# control_board.net
KiCad netlist of a schematic drawn in EAGLE
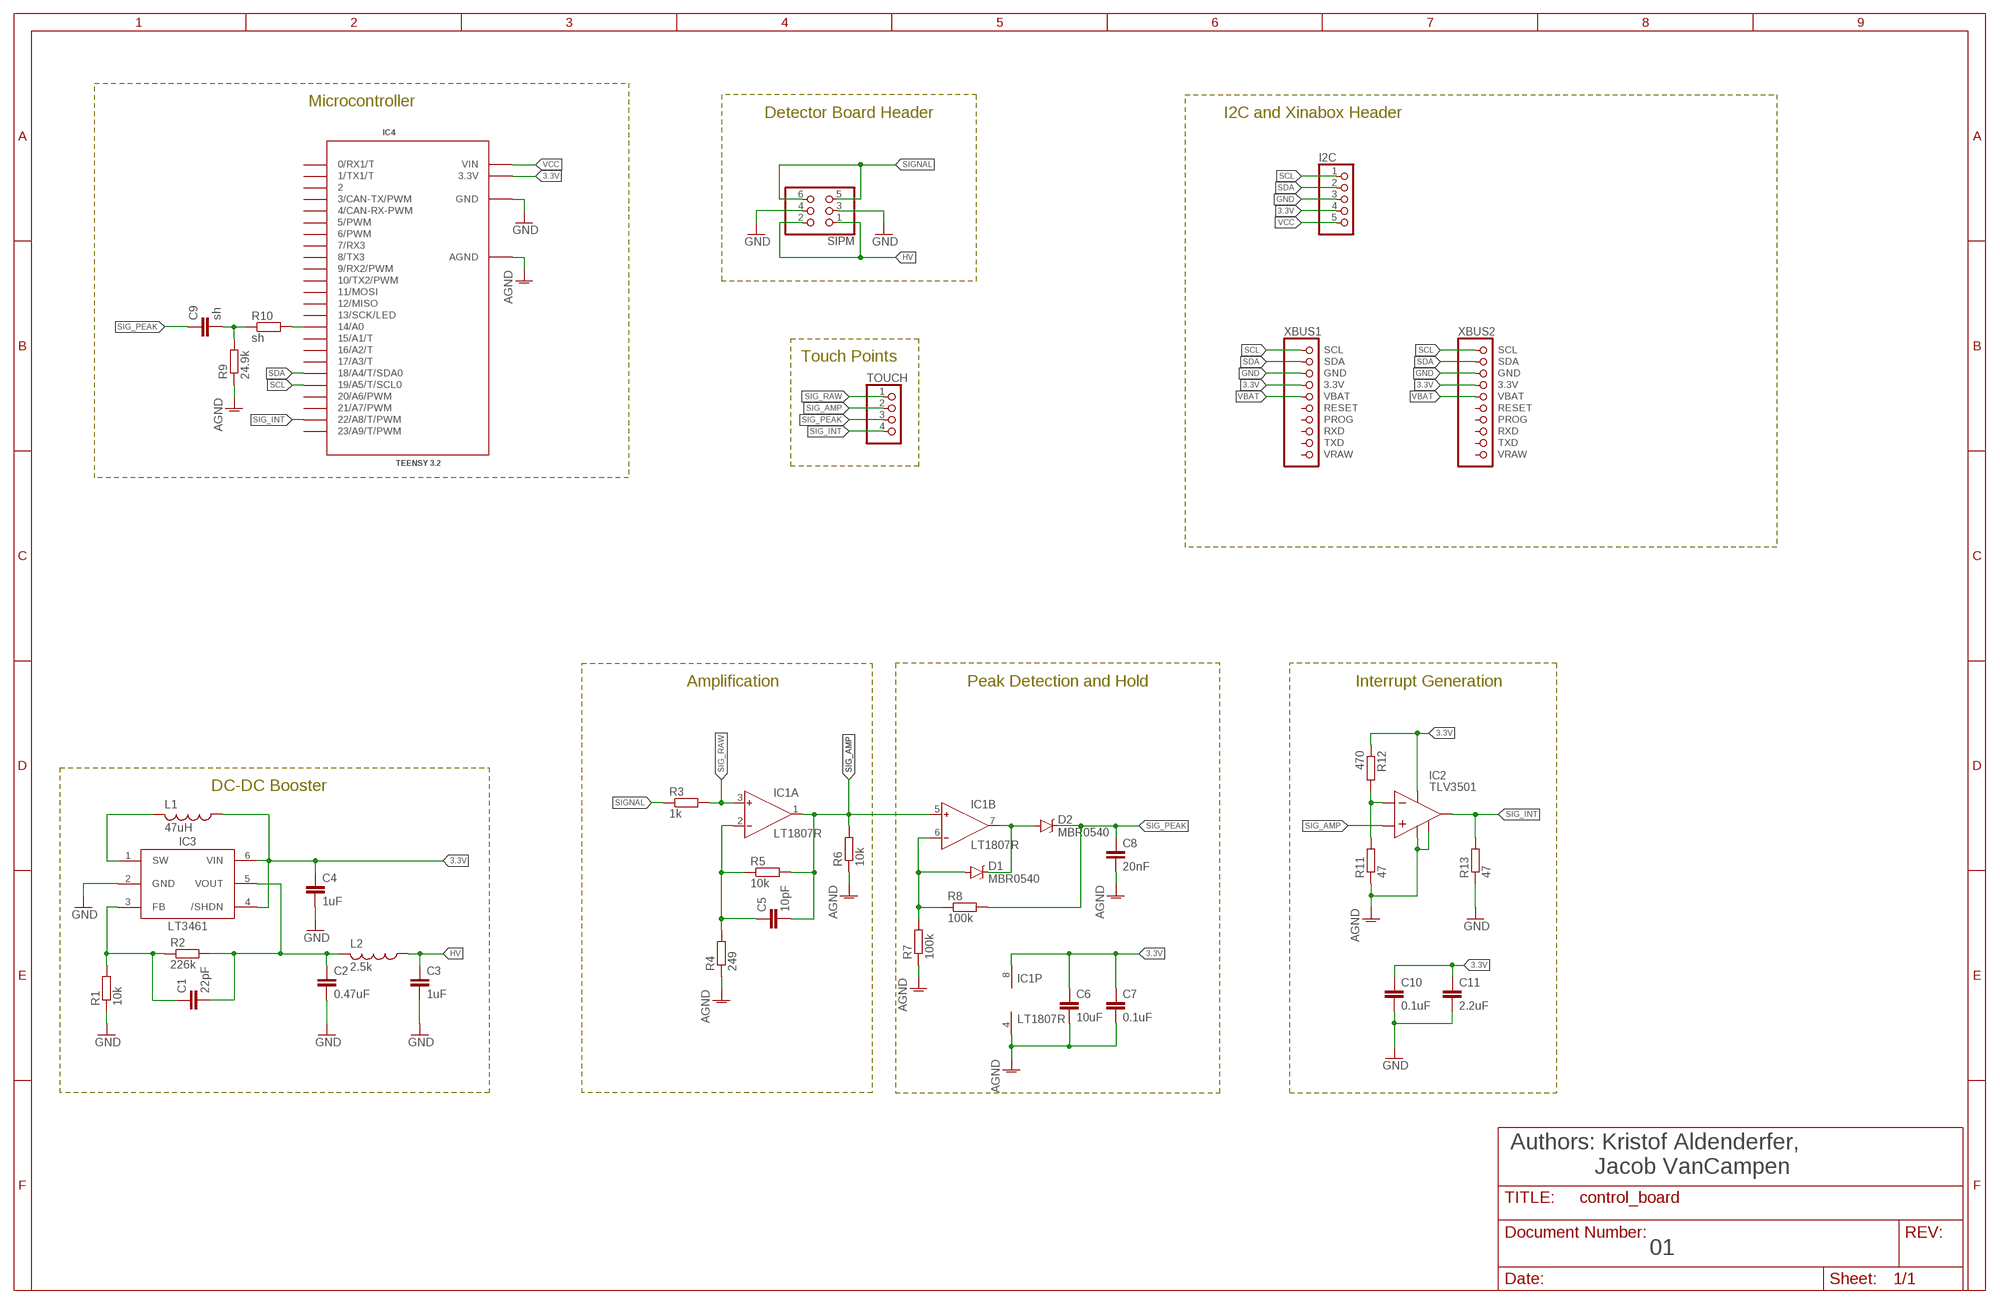
[diagram p0: schematic, sheet 1]

(export (version "E")
  (design (tool "Eeschema 10.0.6"))
  (components
    (comp (ref "C1")
      (value "22pF")
      (footprint "eagle-import:C0805K")
      (libsource (lib "eagle-import") (part "C-EUC0805K"))
    )
    (comp (ref "C2")
      (value "0.47uF")
      (footprint "eagle-import:C0805K")
      (libsource (lib "eagle-import") (part "C-EUC0805K"))
    )
    (comp (ref "C3")
      (value "1uF")
      (footprint "eagle-import:C0805K")
      (libsource (lib "eagle-import") (part "C-EUC0805K"))
    )
    (comp (ref "C4")
      (value "1uF")
      (footprint "eagle-import:C0805K")
      (libsource (lib "eagle-import") (part "C-EUC0805K"))
    )
    (comp (ref "C5")
      (value "10pF")
      (footprint "eagle-import:C0805K")
      (libsource (lib "eagle-import") (part "C-EUC0805K"))
    )
    (comp (ref "C6")
      (value "10uF")
      (footprint "eagle-import:C0805K")
      (libsource (lib "eagle-import") (part "C-EUC0805K"))
    )
    (comp (ref "C7")
      (value "0.1uF")
      (footprint "eagle-import:C0805K")
      (libsource (lib "eagle-import") (part "C-EUC0805K"))
    )
    (comp (ref "C8")
      (value "20nF")
      (footprint "eagle-import:C0805K")
      (libsource (lib "eagle-import") (part "C-EUC0805K"))
    )
    (comp (ref "C9")
      (value "sh")
      (footprint "eagle-import:C0805K")
      (libsource (lib "eagle-import") (part "C-EUC0805K"))
    )
    (comp (ref "C10")
      (value "0.1uF")
      (footprint "eagle-import:C0805")
      (libsource (lib "eagle-import") (part "rcl_334_C-EUC0805"))
    )
    (comp (ref "C11")
      (value "2.2uF")
      (footprint "eagle-import:C0805")
      (libsource (lib "eagle-import") (part "rcl_334_C-EUC0805"))
    )
    (comp (ref "D1")
      (value "MBR0540")
      (footprint "eagle-import:SMA-DIODE")
      (libsource (lib "eagle-import") (part "DIODE-SCHOTTKY-B340A"))
    )
    (comp (ref "D2")
      (value "MBR0540")
      (footprint "eagle-import:SMA-DIODE")
      (libsource (lib "eagle-import") (part "DIODE-SCHOTTKY-B340A"))
    )
    (comp (ref "I2C")
      (value "PINHD-1X5")
      (footprint "eagle-import:1X05")
      (libsource (lib "eagle-import") (part "PINHD-1X5"))
    )
    (comp (ref "IC1")
      (value "LT1807R")
      (footprint "eagle-import:SO8")
      (fields (field (name "MF") "ALTERA CORPORATION") (field (name "MPN") "AD746JRZ"))
      (libsource (lib "eagle-import") (part "LT1807R"))
    )
    (comp (ref "IC2")
      (value "TLV3501")
      (footprint "eagle-import:SOT23-6")
      (libsource (lib "eagle-import") (part "TLV3501"))
    )
    (comp (ref "IC3")
      (value "LT3461")
      (footprint "eagle-import:SOT23-6")
      (libsource (lib "eagle-import") (part "LT3461"))
    )
    (comp (ref "IC4")
      (value "TEENSY 3.2")
      (footprint "eagle-import:TEENSY_3.2_NO_BOTTOM")
      (libsource (lib "eagle-import") (part "TEENSY_3.2_NO_BOTTOM"))
    )
    (comp (ref "L1")
      (value "47uH")
      (footprint "eagle-import:L3225M")
      (libsource (lib "eagle-import") (part "rcl_334_L-USL3225M"))
    )
    (comp (ref "L2")
      (value "2.5k")
      (footprint "eagle-import:L2012C")
      (libsource (lib "eagle-import") (part "L-USL2012C"))
    )
    (comp (ref "R1")
      (value "10k")
      (footprint "eagle-import:M0805")
      (libsource (lib "eagle-import") (part "R-EU_M0805"))
    )
    (comp (ref "R2")
      (value "226k")
      (footprint "eagle-import:M0805")
      (libsource (lib "eagle-import") (part "R-EU_M0805"))
    )
    (comp (ref "R3")
      (value "1k")
      (footprint "eagle-import:M0805")
      (libsource (lib "eagle-import") (part "R-EU_M0805"))
    )
    (comp (ref "R4")
      (value "249")
      (footprint "eagle-import:M0805")
      (libsource (lib "eagle-import") (part "R-EU_M0805"))
    )
    (comp (ref "R5")
      (value "10k")
      (footprint "eagle-import:M0805")
      (libsource (lib "eagle-import") (part "R-EU_M0805"))
    )
    (comp (ref "R6")
      (value "10k")
      (footprint "eagle-import:M0805")
      (libsource (lib "eagle-import") (part "R-EU_M0805"))
    )
    (comp (ref "R7")
      (value "100k")
      (footprint "eagle-import:M0805")
      (libsource (lib "eagle-import") (part "R-EU_M0805"))
    )
    (comp (ref "R8")
      (value "100k")
      (footprint "eagle-import:M0805")
      (libsource (lib "eagle-import") (part "R-EU_M0805"))
    )
    (comp (ref "R9")
      (value "24.9k")
      (footprint "eagle-import:M0805")
      (libsource (lib "eagle-import") (part "R-EU_M0805"))
    )
    (comp (ref "R10")
      (value "sh")
      (footprint "eagle-import:M0805")
      (libsource (lib "eagle-import") (part "R-EU_M0805"))
    )
    (comp (ref "R11")
      (value "47")
      (footprint "eagle-import:M0805")
      (libsource (lib "eagle-import") (part "resistor_348_R-EU_M0805"))
    )
    (comp (ref "R12")
      (value "470")
      (footprint "eagle-import:M0805")
      (libsource (lib "eagle-import") (part "resistor_348_R-EU_M0805"))
    )
    (comp (ref "R13")
      (value "47")
      (footprint "eagle-import:M0805")
      (libsource (lib "eagle-import") (part "resistor_348_R-EU_M0805"))
    )
    (comp (ref "SIPM")
      (value "PINHD-2X3")
      (footprint "eagle-import:2X03")
      (libsource (lib "eagle-import") (part "PINHD-2X3"))
    )
    (comp (ref "TOUCH")
      (value "PINHD-1X4")
      (footprint "eagle-import:1X04")
      (libsource (lib "eagle-import") (part "PINHD-1X4"))
    )
    (comp (ref "XBUS1")
      (value "XINABOX-XBUS")
      (footprint "eagle-import:XBUS_2X05_PAD")
      (libsource (lib "eagle-import") (part "XINABOX-XBUS"))
    )
    (comp (ref "XBUS2")
      (value "XINABOX-XBUS")
      (footprint "eagle-import:XBUS_2X05_PAD")
      (libsource (lib "eagle-import") (part "XINABOX-XBUS"))
    )
  )
  (nets
    (net (code "1") (name "3.3V") (class "Default")
      (node (ref "C10") (pin "1") (pinfunction "1_1") (pintype "passive"))
      (node (ref "C11") (pin "1") (pinfunction "1_1") (pintype "passive"))
      (node (ref "C4") (pin "1") (pinfunction "1_1") (pintype "passive"))
      (node (ref "C6") (pin "1") (pinfunction "1_1") (pintype "passive"))
      (node (ref "C7") (pin "1") (pinfunction "1_1") (pintype "passive"))
      (node (ref "I2C") (pin "4") (pinfunction "4_4") (pintype "passive"))
      (node (ref "IC1") (pin "8") (pinfunction "V+_8") (pintype "power_in"))
      (node (ref "IC2") (pin "P$4") (pinfunction "V+_P$4") (pintype "bidirectional"))
      (node (ref "IC3") (pin "4") (pinfunction "/SHDN_4") (pintype "input"))
      (node (ref "IC3") (pin "6") (pinfunction "VIN_6") (pintype "input"))
      (node (ref "IC4") (pin "3.3V") (pinfunction "3.3V_3.3V") (pintype "power_in"))
      (node (ref "L1") (pin "1") (pinfunction "1_1") (pintype "passive"))
      (node (ref "R12") (pin "1") (pinfunction "1_1") (pintype "passive"))
      (node (ref "XBUS1") (pin "VCC") (pinfunction "3.3V_VCC") (pintype "passive"))
      (node (ref "XBUS2") (pin "VCC") (pinfunction "3.3V_VCC") (pintype "passive"))
    )
    (net (code "2") (name "AGND") (class "Default")
      (node (ref "C6") (pin "2") (pinfunction "2_2") (pintype "passive"))
      (node (ref "C7") (pin "2") (pinfunction "2_2") (pintype "passive"))
      (node (ref "C8") (pin "2") (pinfunction "2_2") (pintype "passive"))
      (node (ref "IC1") (pin "4") (pinfunction "V-_4") (pintype "power_in"))
      (node (ref "IC2") (pin "P$2") (pinfunction "V-_P$2") (pintype "bidirectional"))
      (node (ref "IC2") (pin "P$6") (pinfunction "SHDN_P$6") (pintype "bidirectional"))
      (node (ref "IC4") (pin "AGND") (pinfunction "AGND_AGND") (pintype "power_in"))
      (node (ref "R11") (pin "1") (pinfunction "1_1") (pintype "passive"))
      (node (ref "R4") (pin "1") (pinfunction "1_1") (pintype "passive"))
      (node (ref "R6") (pin "1") (pinfunction "1_1") (pintype "passive"))
      (node (ref "R7") (pin "1") (pinfunction "1_1") (pintype "passive"))
      (node (ref "R9") (pin "1") (pinfunction "1_1") (pintype "passive"))
    )
    (net (code "3") (name "GND") (class "Default")
      (node (ref "C10") (pin "2") (pinfunction "2_2") (pintype "passive"))
      (node (ref "C11") (pin "2") (pinfunction "2_2") (pintype "passive"))
      (node (ref "C2") (pin "2") (pinfunction "2_2") (pintype "passive"))
      (node (ref "C3") (pin "2") (pinfunction "2_2") (pintype "passive"))
      (node (ref "C4") (pin "2") (pinfunction "2_2") (pintype "passive"))
      (node (ref "I2C") (pin "3") (pinfunction "3_3") (pintype "passive"))
      (node (ref "IC3") (pin "2") (pinfunction "GND_2") (pintype "power_in"))
      (node (ref "IC4") (pin "GND") (pinfunction "GND_GND") (pintype "power_in"))
      (node (ref "R1") (pin "1") (pinfunction "1_1") (pintype "passive"))
      (node (ref "R13") (pin "1") (pinfunction "1_1") (pintype "passive"))
      (node (ref "SIPM") (pin "3") (pinfunction "3_3") (pintype "passive"))
      (node (ref "SIPM") (pin "4") (pinfunction "4_4") (pintype "passive"))
      (node (ref "XBUS1") (pin "GND") (pinfunction "GND_GND") (pintype "passive"))
      (node (ref "XBUS2") (pin "GND") (pinfunction "GND_GND") (pintype "passive"))
    )
    (net (code "4") (name "HV") (class "Default")
      (node (ref "C3") (pin "1") (pinfunction "1_1") (pintype "passive"))
      (node (ref "L2") (pin "1") (pinfunction "1_1") (pintype "passive"))
      (node (ref "SIPM") (pin "1") (pinfunction "1_1") (pintype "passive"))
      (node (ref "SIPM") (pin "2") (pinfunction "2_2") (pintype "passive"))
    )
    (net (code "5") (name "Net-(C9-Pad2)") (class "Default")
      (node (ref "C9") (pin "2") (pinfunction "2_2") (pintype "passive"))
      (node (ref "R10") (pin "1") (pinfunction "1_1") (pintype "passive"))
      (node (ref "R9") (pin "2") (pinfunction "2_2") (pintype "passive"))
    )
    (net (code "6") (name "Net-(IC1A-IN-)") (class "Default")
      (node (ref "C5") (pin "1") (pinfunction "1_1") (pintype "passive"))
      (node (ref "IC1") (pin "2") (pinfunction "IN-_2") (pintype "input"))
      (node (ref "R4") (pin "2") (pinfunction "2_2") (pintype "passive"))
      (node (ref "R5") (pin "1") (pinfunction "1_1") (pintype "passive"))
    )
    (net (code "7") (name "Net-(IC1B-IN-)") (class "Default")
      (node (ref "D1") (pin "A") (pinfunction "A_A") (pintype "passive"))
      (node (ref "IC1") (pin "6") (pinfunction "IN-_6") (pintype "input"))
      (node (ref "R7") (pin "2") (pinfunction "2_2") (pintype "passive"))
      (node (ref "R8") (pin "1") (pinfunction "1_1") (pintype "passive"))
    )
    (net (code "8") (name "Net-(IC1B-OUT)") (class "Default")
      (node (ref "D1") (pin "C") (pinfunction "C_C") (pintype "passive"))
      (node (ref "D2") (pin "A") (pinfunction "A_A") (pintype "passive"))
      (node (ref "IC1") (pin "7") (pinfunction "OUT_7") (pintype "output"))
    )
    (net (code "9") (name "Net-(IC2-IN-)") (class "Default")
      (node (ref "IC2") (pin "P$1") (pinfunction "IN-_P$1") (pintype "bidirectional"))
      (node (ref "R11") (pin "2") (pinfunction "2_2") (pintype "passive"))
      (node (ref "R12") (pin "2") (pinfunction "2_2") (pintype "passive"))
    )
    (net (code "10") (name "Net-(IC3-FB)") (class "Default")
      (node (ref "C1") (pin "1") (pinfunction "1_1") (pintype "passive"))
      (node (ref "IC3") (pin "3") (pinfunction "FB_3") (pintype "input"))
      (node (ref "R1") (pin "2") (pinfunction "2_2") (pintype "passive"))
      (node (ref "R2") (pin "1") (pinfunction "1_1") (pintype "passive"))
    )
    (net (code "11") (name "Net-(IC3-SW)") (class "Default")
      (node (ref "IC3") (pin "1") (pinfunction "SW_1") (pintype "output"))
      (node (ref "L1") (pin "2") (pinfunction "2_2") (pintype "passive"))
    )
    (net (code "12") (name "Net-(IC3-VOUT)") (class "Default")
      (node (ref "C1") (pin "2") (pinfunction "2_2") (pintype "passive"))
      (node (ref "C2") (pin "1") (pinfunction "1_1") (pintype "passive"))
      (node (ref "IC3") (pin "5") (pinfunction "VOUT_5") (pintype "output"))
      (node (ref "L2") (pin "2") (pinfunction "2_2") (pintype "passive"))
      (node (ref "R2") (pin "2") (pinfunction "2_2") (pintype "passive"))
    )
    (net (code "13") (name "Net-(IC4-Pad14{slash}A0)") (class "Default")
      (node (ref "IC4") (pin "14/A0") (pinfunction "14/A0_14/A0") (pintype "bidirectional"))
      (node (ref "R10") (pin "2") (pinfunction "2_2") (pintype "passive"))
    )
    (net (code "14") (name "SCL") (class "Default")
      (node (ref "I2C") (pin "1") (pinfunction "1_1") (pintype "passive"))
      (node (ref "IC4") (pin "19/A5") (pinfunction "19/A5/T/SCL0_19/A5") (pintype "bidirectional"))
      (node (ref "XBUS1") (pin "SCL") (pinfunction "SCL_SCL") (pintype "passive"))
      (node (ref "XBUS2") (pin "SCL") (pinfunction "SCL_SCL") (pintype "passive"))
    )
    (net (code "15") (name "SDA") (class "Default")
      (node (ref "I2C") (pin "2") (pinfunction "2_2") (pintype "passive"))
      (node (ref "IC4") (pin "18/A4") (pinfunction "18/A4/T/SDA0_18/A4") (pintype "bidirectional"))
      (node (ref "XBUS1") (pin "SDA") (pinfunction "SDA_SDA") (pintype "passive"))
      (node (ref "XBUS2") (pin "SDA") (pinfunction "SDA_SDA") (pintype "passive"))
    )
    (net (code "16") (name "SIGNAL") (class "Default")
      (node (ref "R3") (pin "1") (pinfunction "1_1") (pintype "passive"))
      (node (ref "SIPM") (pin "5") (pinfunction "5_5") (pintype "passive"))
      (node (ref "SIPM") (pin "6") (pinfunction "6_6") (pintype "passive"))
    )
    (net (code "17") (name "SIG_AMP") (class "Default")
      (node (ref "C5") (pin "2") (pinfunction "2_2") (pintype "passive"))
      (node (ref "IC1") (pin "1") (pinfunction "OUT_1") (pintype "output"))
      (node (ref "IC1") (pin "5") (pinfunction "IN+_5") (pintype "input"))
      (node (ref "IC2") (pin "P$3") (pinfunction "IN+_P$3") (pintype "bidirectional"))
      (node (ref "R5") (pin "2") (pinfunction "2_2") (pintype "passive"))
      (node (ref "R6") (pin "2") (pinfunction "2_2") (pintype "passive"))
      (node (ref "TOUCH") (pin "2") (pinfunction "2_2") (pintype "passive"))
    )
    (net (code "18") (name "SIG_INT") (class "Default")
      (node (ref "IC2") (pin "P$5") (pinfunction "OUT_P$5") (pintype "bidirectional"))
      (node (ref "IC4") (pin "22/A8") (pinfunction "22/A8/T/PWM_22/A8") (pintype "bidirectional"))
      (node (ref "R13") (pin "2") (pinfunction "2_2") (pintype "passive"))
      (node (ref "TOUCH") (pin "4") (pinfunction "4_4") (pintype "passive"))
    )
    (net (code "19") (name "SIG_PEAK") (class "Default")
      (node (ref "C8") (pin "1") (pinfunction "1_1") (pintype "passive"))
      (node (ref "C9") (pin "1") (pinfunction "1_1") (pintype "passive"))
      (node (ref "D2") (pin "C") (pinfunction "C_C") (pintype "passive"))
      (node (ref "R8") (pin "2") (pinfunction "2_2") (pintype "passive"))
      (node (ref "TOUCH") (pin "3") (pinfunction "3_3") (pintype "passive"))
    )
    (net (code "20") (name "SIG_RAW") (class "Default")
      (node (ref "IC1") (pin "3") (pinfunction "IN+_3") (pintype "input"))
      (node (ref "R3") (pin "2") (pinfunction "2_2") (pintype "passive"))
      (node (ref "TOUCH") (pin "1") (pinfunction "1_1") (pintype "passive"))
    )
    (net (code "21") (name "VBAT") (class "Default")
      (node (ref "XBUS1") (pin "VBAT") (pinfunction "VBAT_VBAT") (pintype "passive"))
      (node (ref "XBUS2") (pin "VBAT") (pinfunction "VBAT_VBAT") (pintype "passive"))
    )
    (net (code "22") (name "VCC") (class "Default")
      (node (ref "I2C") (pin "5") (pinfunction "5_5") (pintype "passive"))
      (node (ref "IC4") (pin "VIN") (pinfunction "VIN_VIN") (pintype "power_in"))
    )
    (net (code "23") (name "unconnected-(IC4-0{slash}RX1{slash}T-Pad0)") (class "Default")
      (node (ref "IC4") (pin "0") (pinfunction "0/RX1/T_0") (pintype "bidirectional"))
    )
    (net (code "24") (name "unconnected-(IC4-1{slash}TX1{slash}T-Pad1)") (class "Default")
      (node (ref "IC4") (pin "1") (pinfunction "1/TX1/T_1") (pintype "bidirectional"))
    )
    (net (code "25") (name "unconnected-(IC4-3{slash}CAN-TX{slash}PWM-Pad3)") (class "Default")
      (node (ref "IC4") (pin "3") (pinfunction "3/CAN-TX/PWM_3") (pintype "bidirectional"))
    )
    (net (code "26") (name "unconnected-(IC4-4{slash}CAN-RX-PWM-Pad4)") (class "Default")
      (node (ref "IC4") (pin "4") (pinfunction "4/CAN-RX-PWM_4") (pintype "bidirectional"))
    )
    (net (code "27") (name "unconnected-(IC4-5{slash}PWM-Pad5)") (class "Default")
      (node (ref "IC4") (pin "5") (pinfunction "5/PWM_5") (pintype "bidirectional"))
    )
    (net (code "28") (name "unconnected-(IC4-6{slash}PWM-Pad6)") (class "Default")
      (node (ref "IC4") (pin "6") (pinfunction "6/PWM_6") (pintype "bidirectional"))
    )
    (net (code "29") (name "unconnected-(IC4-7{slash}RX3-Pad7)") (class "Default")
      (node (ref "IC4") (pin "7") (pinfunction "7/RX3_7") (pintype "bidirectional"))
    )
    (net (code "30") (name "unconnected-(IC4-8{slash}TX3-Pad8)") (class "Default")
      (node (ref "IC4") (pin "8") (pinfunction "8/TX3_8") (pintype "bidirectional"))
    )
    (net (code "31") (name "unconnected-(IC4-9{slash}RX2{slash}PWM-Pad9)") (class "Default")
      (node (ref "IC4") (pin "9") (pinfunction "9/RX2/PWM_9") (pintype "bidirectional"))
    )
    (net (code "32") (name "unconnected-(IC4-10{slash}TX2{slash}PWM-Pad10)") (class "Default")
      (node (ref "IC4") (pin "10") (pinfunction "10/TX2/PWM_10") (pintype "bidirectional"))
    )
    (net (code "33") (name "unconnected-(IC4-11{slash}MOSI-Pad11)") (class "Default")
      (node (ref "IC4") (pin "11") (pinfunction "11/MOSI_11") (pintype "bidirectional"))
    )
    (net (code "34") (name "unconnected-(IC4-12{slash}MISO-Pad12)") (class "Default")
      (node (ref "IC4") (pin "12") (pinfunction "12/MISO_12") (pintype "bidirectional"))
    )
    (net (code "35") (name "unconnected-(IC4-13{slash}SCK{slash}LED-Pad13)") (class "Default")
      (node (ref "IC4") (pin "13") (pinfunction "13/SCK/LED_13") (pintype "bidirectional"))
    )
    (net (code "36") (name "unconnected-(IC4-15{slash}A1{slash}T-Pad15{slash}A1)") (class "Default")
      (node (ref "IC4") (pin "15/A1") (pinfunction "15/A1/T_15/A1") (pintype "bidirectional"))
    )
    (net (code "37") (name "unconnected-(IC4-16{slash}A2{slash}T-Pad16{slash}A2)") (class "Default")
      (node (ref "IC4") (pin "16/A2") (pinfunction "16/A2/T_16/A2") (pintype "bidirectional"))
    )
    (net (code "38") (name "unconnected-(IC4-17{slash}A3{slash}T-Pad17{slash}A3)") (class "Default")
      (node (ref "IC4") (pin "17/A3") (pinfunction "17/A3/T_17/A3") (pintype "bidirectional"))
    )
    (net (code "39") (name "unconnected-(IC4-20{slash}A6{slash}PWM-Pad20{slash}A6)") (class "Default")
      (node (ref "IC4") (pin "20/A6") (pinfunction "20/A6/PWM_20/A6") (pintype "bidirectional"))
    )
    (net (code "40") (name "unconnected-(IC4-21{slash}A7{slash}PWM-Pad21{slash}A7)") (class "Default")
      (node (ref "IC4") (pin "21/A7") (pinfunction "21/A7/PWM_21/A7") (pintype "bidirectional"))
    )
    (net (code "41") (name "unconnected-(IC4-23{slash}A9{slash}T{slash}PWM-Pad23{slash}A9)") (class "Default")
      (node (ref "IC4") (pin "23/A9") (pinfunction "23/A9/T/PWM_23/A9") (pintype "bidirectional"))
    )
    (net (code "42") (name "unconnected-(IC4-Pad2)") (class "Default")
      (node (ref "IC4") (pin "2") (pinfunction "2_2") (pintype "bidirectional"))
    )
    (net (code "43") (name "unconnected-(XBUS1-PadPROG)") (class "Default")
      (node (ref "XBUS1") (pin "PROG") (pinfunction "PROG_PROG") (pintype "passive"))
    )
    (net (code "44") (name "unconnected-(XBUS1-PadRESET)") (class "Default")
      (node (ref "XBUS1") (pin "RESET") (pinfunction "RESET_RESET") (pintype "passive"))
    )
    (net (code "45") (name "unconnected-(XBUS1-PadRXD)") (class "Default")
      (node (ref "XBUS1") (pin "RXD") (pinfunction "RXD_RXD") (pintype "passive"))
    )
    (net (code "46") (name "unconnected-(XBUS1-PadTXD)") (class "Default")
      (node (ref "XBUS1") (pin "TXD") (pinfunction "TXD_TXD") (pintype "passive"))
    )
    (net (code "47") (name "unconnected-(XBUS1-PadVRAW)") (class "Default")
      (node (ref "XBUS1") (pin "VRAW") (pinfunction "VRAW_VRAW") (pintype "passive"))
    )
    (net (code "48") (name "unconnected-(XBUS2-PadPROG)") (class "Default")
      (node (ref "XBUS2") (pin "PROG") (pinfunction "PROG_PROG") (pintype "passive"))
    )
    (net (code "49") (name "unconnected-(XBUS2-PadRESET)") (class "Default")
      (node (ref "XBUS2") (pin "RESET") (pinfunction "RESET_RESET") (pintype "passive"))
    )
    (net (code "50") (name "unconnected-(XBUS2-PadRXD)") (class "Default")
      (node (ref "XBUS2") (pin "RXD") (pinfunction "RXD_RXD") (pintype "passive"))
    )
    (net (code "51") (name "unconnected-(XBUS2-PadTXD)") (class "Default")
      (node (ref "XBUS2") (pin "TXD") (pinfunction "TXD_TXD") (pintype "passive"))
    )
    (net (code "52") (name "unconnected-(XBUS2-PadVRAW)") (class "Default")
      (node (ref "XBUS2") (pin "VRAW") (pinfunction "VRAW_VRAW") (pintype "passive"))
    )
  )
)
